# JacdacPower_50.net
KiCad netlist of a schematic drawn in Altium Designer
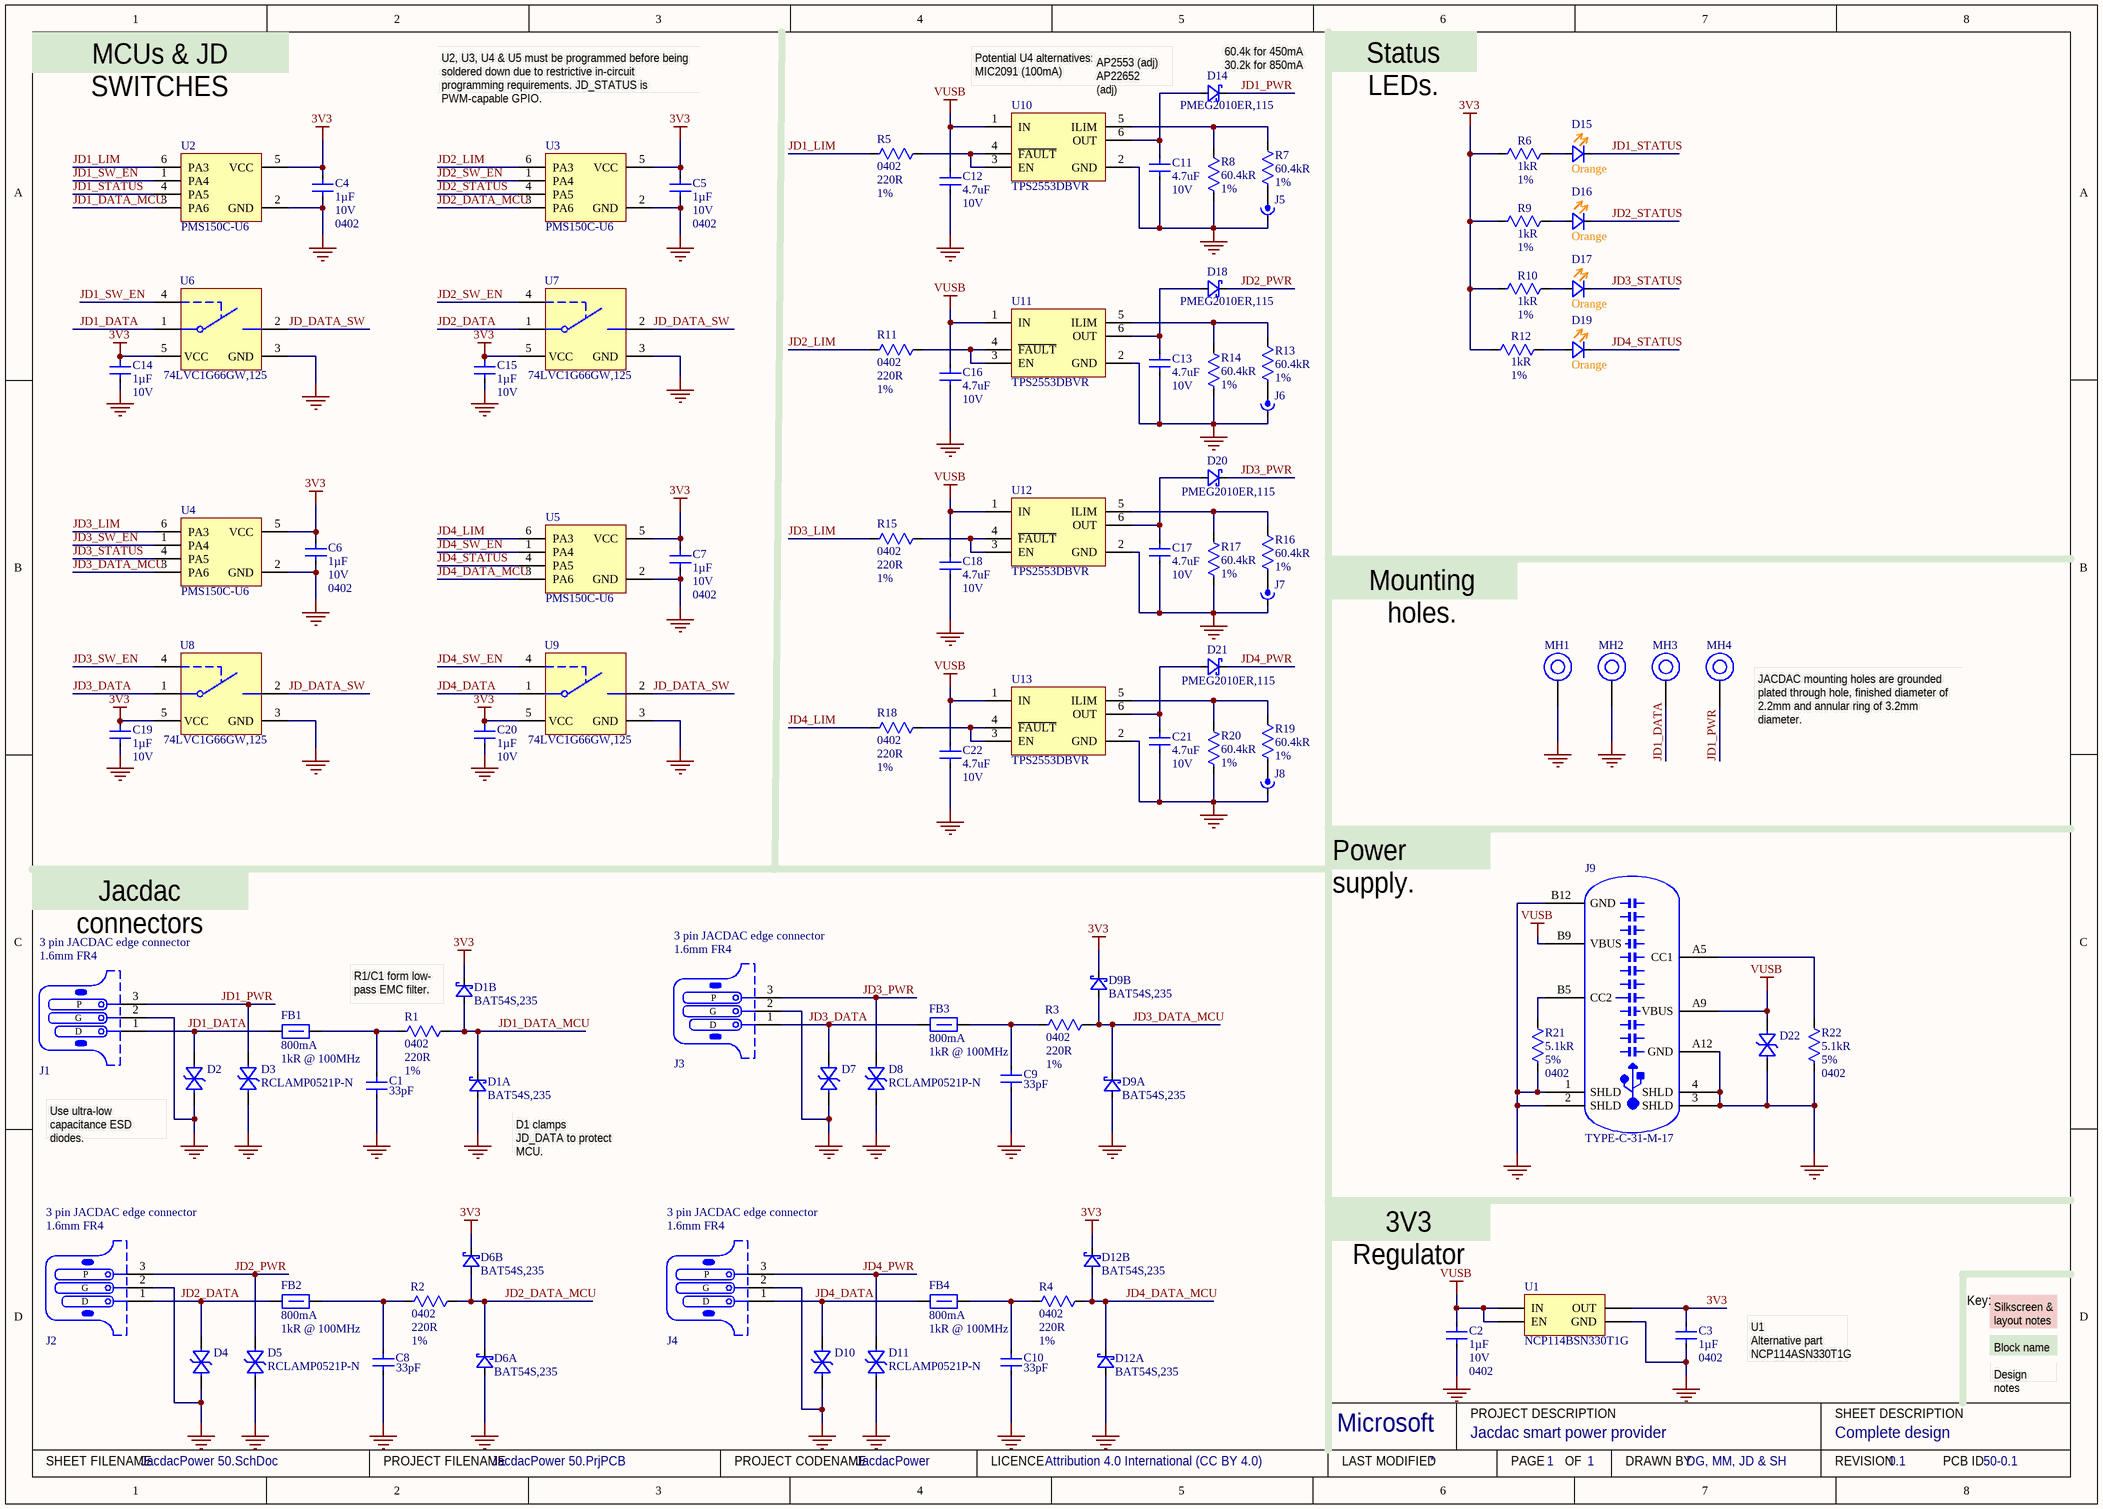
[diagram p0: JacdacPower 50.SchDoc]

(export (version "E")
  (design (tool "Eeschema 10.0.6"))
  (components
    (comp (ref "C1")
      (value "CL05C330JB5NNNC")
      (footprint "C0402_0.55MM - without outline")
      (description "CAP CER 33PF 50V C0G/NP0 0402")
      (fields
        (field (name "MANUFACTURER") "Samsung")
        (field (name "TOLERANCE") "5%")
        (field (name "CAPACITANCE") "33pF")
      )
      (libsource (lib "Samsung") (part "CL05C330JB5NNNC"))
    )
    (comp (ref "C2")
      (value "CL05A105KP5NNNC")
      (footprint "C0402_0.55MM - without outline")
      (description "CAP CER 1UF 10V X5R 0402")
      (fields
        (field (name "MANUFACTURER") "Samsung")
        (field (name "TOLERANCE") "10%")
        (field (name "CAPACITANCE") "1µF")
        (field (name "VOLTAGE RATING") "10V")
        (field (name "CASE CODE (IMPERIAL)") "0402")
      )
      (libsource (lib "Samsung") (part "CL05A105KP5NNNC"))
    )
    (comp (ref "C3")
      (value "CL05A105KP5NNNC")
      (footprint "C0402_0.55MM - without outline")
      (description "CAP CER 1UF 10V X5R 0402")
      (fields
        (field (name "MANUFACTURER") "Samsung")
        (field (name "TOLERANCE") "10%")
        (field (name "CAPACITANCE") "1µF")
        (field (name "CASE CODE (IMPERIAL)") "0402")
      )
      (libsource (lib "Samsung") (part "CL05A105KP5NNNC"))
    )
    (comp (ref "C4")
      (value "CL05A105KP5NNNC")
      (footprint "C0402_0.55MM - without outline")
      (description "CAP CER 1UF 10V X5R 0402")
      (fields
        (field (name "MANUFACTURER") "Samsung")
        (field (name "TOLERANCE") "10%")
        (field (name "CAPACITANCE") "1µF")
        (field (name "VOLTAGE RATING") "10V")
        (field (name "CASE CODE (IMPERIAL)") "0402")
      )
      (libsource (lib "Samsung") (part "CL05A105KP5NNNC"))
    )
    (comp (ref "C5")
      (value "CL05A105KP5NNNC")
      (footprint "C0402_0.55MM - without outline")
      (description "CAP CER 1UF 10V X5R 0402")
      (fields
        (field (name "MANUFACTURER") "Samsung")
        (field (name "TOLERANCE") "10%")
        (field (name "CAPACITANCE") "1µF")
        (field (name "VOLTAGE RATING") "10V")
        (field (name "CASE CODE (IMPERIAL)") "0402")
      )
      (libsource (lib "Samsung") (part "CL05A105KP5NNNC"))
    )
    (comp (ref "C6")
      (value "CL05A105KP5NNNC")
      (footprint "C0402_0.55MM - without outline")
      (description "CAP CER 1UF 10V X5R 0402")
      (fields
        (field (name "MANUFACTURER") "Samsung")
        (field (name "TOLERANCE") "10%")
        (field (name "CAPACITANCE") "1µF")
        (field (name "VOLTAGE RATING") "10V")
        (field (name "CASE CODE (IMPERIAL)") "0402")
      )
      (libsource (lib "Samsung") (part "CL05A105KP5NNNC"))
    )
    (comp (ref "C7")
      (value "CL05A105KP5NNNC")
      (footprint "C0402_0.55MM - without outline")
      (description "CAP CER 1UF 10V X5R 0402")
      (fields
        (field (name "MANUFACTURER") "Samsung")
        (field (name "TOLERANCE") "10%")
        (field (name "CAPACITANCE") "1µF")
        (field (name "VOLTAGE RATING") "10V")
        (field (name "CASE CODE (IMPERIAL)") "0402")
      )
      (libsource (lib "Samsung") (part "CL05A105KP5NNNC"))
    )
    (comp (ref "C8")
      (value "CL05C330JB5NNNC")
      (footprint "C0402_0.55MM - without outline")
      (description "CAP CER 33PF 50V C0G/NP0 0402")
      (fields
        (field (name "MANUFACTURER") "Samsung")
        (field (name "TOLERANCE") "5%")
        (field (name "CAPACITANCE") "33pF")
      )
      (libsource (lib "Samsung") (part "CL05C330JB5NNNC"))
    )
    (comp (ref "C9")
      (value "CL05C330JB5NNNC")
      (footprint "C0402_0.55MM - without outline")
      (description "CAP CER 33PF 50V C0G/NP0 0402")
      (fields
        (field (name "MANUFACTURER") "Samsung")
        (field (name "TOLERANCE") "5%")
        (field (name "CAPACITANCE") "33pF")
      )
      (libsource (lib "Samsung") (part "CL05C330JB5NNNC"))
    )
    (comp (ref "C10")
      (value "CL05C330JB5NNNC")
      (footprint "C0402_0.55MM - without outline")
      (description "CAP CER 33PF 50V C0G/NP0 0402")
      (fields
        (field (name "MANUFACTURER") "Samsung")
        (field (name "TOLERANCE") "5%")
        (field (name "CAPACITANCE") "33pF")
      )
      (libsource (lib "Samsung") (part "CL05C330JB5NNNC"))
    )
    (comp (ref "C11")
      (value "CL05A475MP5NRNC")
      (footprint "R0402 - Without outline")
      (description "CAP CER 4.7UF 10V X5R 0402")
      (fields
        (field (name "MANUFACTURER") "Samsung")
        (field (name "TOLERANCE") "20%")
        (field (name "CAPACITANCE") "4.7uF")
        (field (name "VOLTAGE RATING") "10V")
      )
      (libsource (lib "Samsung") (part "CL05A475MP5NRNC"))
    )
    (comp (ref "C12")
      (value "CL05A475MP5NRNC")
      (footprint "R0402 - Without outline")
      (description "CAP CER 4.7UF 10V X5R 0402")
      (fields
        (field (name "MANUFACTURER") "Samsung")
        (field (name "TOLERANCE") "20%")
        (field (name "CAPACITANCE") "4.7uF")
        (field (name "VOLTAGE RATING") "10V")
      )
      (libsource (lib "Samsung") (part "CL05A475MP5NRNC"))
    )
    (comp (ref "C13")
      (value "CL05A475MP5NRNC")
      (footprint "R0402 - Without outline")
      (description "CAP CER 4.7UF 10V X5R 0402")
      (fields
        (field (name "MANUFACTURER") "Samsung")
        (field (name "TOLERANCE") "20%")
        (field (name "CAPACITANCE") "4.7uF")
        (field (name "VOLTAGE RATING") "10V")
      )
      (libsource (lib "Samsung") (part "CL05A475MP5NRNC"))
    )
    (comp (ref "C14")
      (value "CL05A105KP5NNNC")
      (footprint "C0402_0.55MM - without outline")
      (description "CAP CER 1UF 10V X5R 0402")
      (fields
        (field (name "MANUFACTURER") "Samsung")
        (field (name "TOLERANCE") "10%")
        (field (name "CAPACITANCE") "1µF")
        (field (name "VOLTAGE RATING") "10V")
      )
      (libsource (lib "Samsung") (part "CL05A105KP5NNNC"))
    )
    (comp (ref "C15")
      (value "CL05A105KP5NNNC")
      (footprint "C0402_0.55MM - without outline")
      (description "CAP CER 1UF 10V X5R 0402")
      (fields
        (field (name "MANUFACTURER") "Samsung")
        (field (name "TOLERANCE") "10%")
        (field (name "CAPACITANCE") "1µF")
        (field (name "VOLTAGE RATING") "10V")
      )
      (libsource (lib "Samsung") (part "CL05A105KP5NNNC"))
    )
    (comp (ref "C16")
      (value "CL05A475MP5NRNC")
      (footprint "R0402 - Without outline")
      (description "CAP CER 4.7UF 10V X5R 0402")
      (fields
        (field (name "MANUFACTURER") "Samsung")
        (field (name "TOLERANCE") "20%")
        (field (name "CAPACITANCE") "4.7uF")
        (field (name "VOLTAGE RATING") "10V")
      )
      (libsource (lib "Samsung") (part "CL05A475MP5NRNC"))
    )
    (comp (ref "C17")
      (value "CL05A475MP5NRNC")
      (footprint "R0402 - Without outline")
      (description "CAP CER 4.7UF 10V X5R 0402")
      (fields
        (field (name "MANUFACTURER") "Samsung")
        (field (name "TOLERANCE") "20%")
        (field (name "CAPACITANCE") "4.7uF")
        (field (name "VOLTAGE RATING") "10V")
      )
      (libsource (lib "Samsung") (part "CL05A475MP5NRNC"))
    )
    (comp (ref "C18")
      (value "CL05A475MP5NRNC")
      (footprint "R0402 - Without outline")
      (description "CAP CER 4.7UF 10V X5R 0402")
      (fields
        (field (name "MANUFACTURER") "Samsung")
        (field (name "TOLERANCE") "20%")
        (field (name "CAPACITANCE") "4.7uF")
        (field (name "VOLTAGE RATING") "10V")
      )
      (libsource (lib "Samsung") (part "CL05A475MP5NRNC"))
    )
    (comp (ref "C19")
      (value "CL05A105KP5NNNC")
      (footprint "C0402_0.55MM - without outline")
      (description "CAP CER 1UF 10V X5R 0402")
      (fields
        (field (name "MANUFACTURER") "Samsung")
        (field (name "TOLERANCE") "10%")
        (field (name "CAPACITANCE") "1µF")
        (field (name "VOLTAGE RATING") "10V")
      )
      (libsource (lib "Samsung") (part "CL05A105KP5NNNC"))
    )
    (comp (ref "C20")
      (value "CL05A105KP5NNNC")
      (footprint "C0402_0.55MM - without outline")
      (description "CAP CER 1UF 10V X5R 0402")
      (fields
        (field (name "MANUFACTURER") "Samsung")
        (field (name "TOLERANCE") "10%")
        (field (name "CAPACITANCE") "1µF")
        (field (name "VOLTAGE RATING") "10V")
      )
      (libsource (lib "Samsung") (part "CL05A105KP5NNNC"))
    )
    (comp (ref "C21")
      (value "CL05A475MP5NRNC")
      (footprint "R0402 - Without outline")
      (description "CAP CER 4.7UF 10V X5R 0402")
      (fields
        (field (name "MANUFACTURER") "Samsung")
        (field (name "TOLERANCE") "20%")
        (field (name "CAPACITANCE") "4.7uF")
        (field (name "VOLTAGE RATING") "10V")
      )
      (libsource (lib "Samsung") (part "CL05A475MP5NRNC"))
    )
    (comp (ref "C22")
      (value "CL05A475MP5NRNC")
      (footprint "R0402 - Without outline")
      (description "CAP CER 4.7UF 10V X5R 0402")
      (fields
        (field (name "MANUFACTURER") "Samsung")
        (field (name "TOLERANCE") "20%")
        (field (name "CAPACITANCE") "4.7uF")
        (field (name "VOLTAGE RATING") "10V")
      )
      (libsource (lib "Samsung") (part "CL05A475MP5NRNC"))
    )
    (comp (ref "D1")
      (value "BAT54S")
      (footprint "NXP-BAT54S-TO-236AB - without outline")
      (description "DIODE ARRAY SCHOTTKY 30V SOT23")
      (fields (field (name "MANUFACTURER") "Nexperia") (field (name "MANUFACTURER PART NUMBER") "BAT54S,235"))
      (libsource (lib "NXP") (part "BAT54S"))
    )
    (comp (ref "D2")
      (value "RCLAMP0521P-N")
      (footprint "TVS 0402 - without outline")
      (description "Bidirectional 5V (Max) 6V 16V 3.5A (8/20us) 0402 TVS RoHS")
      (fields (field (name "MANUFACTURER") "Born Semiconductor"))
      (libsource (lib "BornSemiconductor") (part "RCLAMP0521P-N"))
    )
    (comp (ref "D3")
      (value "RCLAMP0521P-N")
      (footprint "TVS 0402 - without outline")
      (description "Bidirectional 5V (Max) 6V 16V 3.5A (8/20us) 0402 TVS RoHS")
      (fields
        (field (name "MANUFACTURER") "Born Semiconductor")
        (field (name "MANUFACTURER PART NUMBER") "RCLAMP0521P-N")
      )
      (libsource (lib "BornSemiconductor") (part "RCLAMP0521P-N"))
    )
    (comp (ref "D4")
      (value "RCLAMP0521P-N")
      (footprint "TVS 0402 - without outline")
      (description "Bidirectional 5V (Max) 6V 16V 3.5A (8/20us) 0402 TVS RoHS")
      (fields (field (name "MANUFACTURER") "Born Semiconductor"))
      (libsource (lib "BornSemiconductor") (part "RCLAMP0521P-N"))
    )
    (comp (ref "D5")
      (value "RCLAMP0521P-N")
      (footprint "TVS 0402 - without outline")
      (description "Bidirectional 5V (Max) 6V 16V 3.5A (8/20us) 0402 TVS RoHS")
      (fields
        (field (name "MANUFACTURER") "Born Semiconductor")
        (field (name "MANUFACTURER PART NUMBER") "RCLAMP0521P-N")
      )
      (libsource (lib "BornSemiconductor") (part "RCLAMP0521P-N"))
    )
    (comp (ref "D6")
      (value "BAT54S")
      (footprint "NXP-BAT54S-TO-236AB - without outline")
      (description "DIODE ARRAY SCHOTTKY 30V SOT23")
      (fields (field (name "MANUFACTURER") "Nexperia") (field (name "MANUFACTURER PART NUMBER") "BAT54S,235"))
      (libsource (lib "NXP") (part "BAT54S"))
    )
    (comp (ref "D7")
      (value "RCLAMP0521P-N")
      (footprint "TVS 0402 - without outline")
      (description "Bidirectional 5V (Max) 6V 16V 3.5A (8/20us) 0402 TVS RoHS")
      (fields (field (name "MANUFACTURER") "Born Semiconductor"))
      (libsource (lib "BornSemiconductor") (part "RCLAMP0521P-N"))
    )
    (comp (ref "D8")
      (value "RCLAMP0521P-N")
      (footprint "TVS 0402 - without outline")
      (description "Bidirectional 5V (Max) 6V 16V 3.5A (8/20us) 0402 TVS RoHS")
      (fields
        (field (name "MANUFACTURER") "Born Semiconductor")
        (field (name "MANUFACTURER PART NUMBER") "RCLAMP0521P-N")
      )
      (libsource (lib "BornSemiconductor") (part "RCLAMP0521P-N"))
    )
    (comp (ref "D9")
      (value "BAT54S")
      (footprint "NXP-BAT54S-TO-236AB - without outline")
      (description "DIODE ARRAY SCHOTTKY 30V SOT23")
      (fields (field (name "MANUFACTURER") "Nexperia") (field (name "MANUFACTURER PART NUMBER") "BAT54S,235"))
      (libsource (lib "NXP") (part "BAT54S"))
    )
    (comp (ref "D10")
      (value "RCLAMP0521P-N")
      (footprint "TVS 0402 - without outline")
      (description "Bidirectional 5V (Max) 6V 16V 3.5A (8/20us) 0402 TVS RoHS")
      (fields (field (name "MANUFACTURER") "Born Semiconductor"))
      (libsource (lib "BornSemiconductor") (part "RCLAMP0521P-N"))
    )
    (comp (ref "D11")
      (value "RCLAMP0521P-N")
      (footprint "TVS 0402 - without outline")
      (description "Bidirectional 5V (Max) 6V 16V 3.5A (8/20us) 0402 TVS RoHS")
      (fields
        (field (name "MANUFACTURER") "Born Semiconductor")
        (field (name "MANUFACTURER PART NUMBER") "RCLAMP0521P-N")
      )
      (libsource (lib "BornSemiconductor") (part "RCLAMP0521P-N"))
    )
    (comp (ref "D12")
      (value "BAT54S")
      (footprint "NXP-BAT54S-TO-236AB - without outline")
      (description "DIODE ARRAY SCHOTTKY 30V SOT23")
      (fields (field (name "MANUFACTURER") "Nexperia") (field (name "MANUFACTURER PART NUMBER") "BAT54S,235"))
      (libsource (lib "NXP") (part "BAT54S"))
    )
    (comp (ref "D14")
      (value "PMEG2010ER,115")
      (footprint "SOD-123W")
      (description "NEXPERIA - PMEG2010ER,115 - DIODE, RECT SCH, 20V, 1A, SOD123W")
      (fields
        (field (name "MANUFACTURER") "Nexperia")
        (field (name "MANUFACTURER PART NUMBER") "PMEG2010ER,115")
      )
      (libsource (lib "NXP") (part "PMEG2010ER,115"))
    )
    (comp (ref "D15")
      (value "~")
      (footprint "0603 Orange")
      (description "LED ORANGE DIFFUSED 0603 SMD")
      (fields
        (field (name "MANUFACTURER") "Everlight Elec")
        (field (name "MANUFACTURER PART NUMBER") "19-217/S2C-AQ1R1B/3T")
        (field (name "COLOUR") "Orange")
      )
      (libsource (lib "EverlightElec") (part "19-217/S2C-AQ1R1B/3T"))
    )
    (comp (ref "D16")
      (value "~")
      (footprint "0603 Orange")
      (description "LED ORANGE DIFFUSED 0603 SMD")
      (fields
        (field (name "MANUFACTURER") "Everlight Elec")
        (field (name "MANUFACTURER PART NUMBER") "19-217/S2C-AQ1R1B/3T")
        (field (name "COLOUR") "Orange")
      )
      (libsource (lib "EverlightElec") (part "19-217/S2C-AQ1R1B/3T"))
    )
    (comp (ref "D17")
      (value "~")
      (footprint "0603 Orange")
      (description "LED ORANGE DIFFUSED 0603 SMD")
      (fields
        (field (name "MANUFACTURER") "Everlight Elec")
        (field (name "MANUFACTURER PART NUMBER") "19-217/S2C-AQ1R1B/3T")
        (field (name "COLOUR") "Orange")
      )
      (libsource (lib "EverlightElec") (part "19-217/S2C-AQ1R1B/3T"))
    )
    (comp (ref "D18")
      (value "PMEG2010ER,115")
      (footprint "SOD-123W")
      (description "NEXPERIA - PMEG2010ER,115 - DIODE, RECT SCH, 20V, 1A, SOD123W")
      (fields
        (field (name "MANUFACTURER") "Nexperia")
        (field (name "MANUFACTURER PART NUMBER") "PMEG2010ER,115")
      )
      (libsource (lib "NXP") (part "PMEG2010ER,115"))
    )
    (comp (ref "D19")
      (value "~")
      (footprint "0603 Orange")
      (description "LED ORANGE DIFFUSED 0603 SMD")
      (fields
        (field (name "MANUFACTURER") "Everlight Elec")
        (field (name "MANUFACTURER PART NUMBER") "19-217/S2C-AQ1R1B/3T")
        (field (name "COLOUR") "Orange")
      )
      (libsource (lib "EverlightElec") (part "19-217/S2C-AQ1R1B/3T"))
    )
    (comp (ref "D20")
      (value "PMEG2010ER,115")
      (footprint "SOD-123W")
      (description "NEXPERIA - PMEG2010ER,115 - DIODE, RECT SCH, 20V, 1A, SOD123W")
      (fields
        (field (name "MANUFACTURER") "Nexperia")
        (field (name "MANUFACTURER PART NUMBER") "PMEG2010ER,115")
      )
      (libsource (lib "NXP") (part "PMEG2010ER,115"))
    )
    (comp (ref "D21")
      (value "PMEG2010ER,115")
      (footprint "SOD-123W")
      (description "NEXPERIA - PMEG2010ER,115 - DIODE, RECT SCH, 20V, 1A, SOD123W")
      (fields
        (field (name "MANUFACTURER") "Nexperia")
        (field (name "MANUFACTURER PART NUMBER") "PMEG2010ER,115")
      )
      (libsource (lib "NXP") (part "PMEG2010ER,115"))
    )
    (comp (ref "D22")
      (value "RCLAMP0521P-N")
      (footprint "TVS 0402 - without outline")
      (description "Bidirectional 5V (Max) 6V 16V 3.5A (8/20us) 0402 TVS RoHS")
      (fields (field (name "MANUFACTURER") "Born Semiconductor"))
      (libsource (lib "BornSemiconductor") (part "RCLAMP0521P-N"))
    )
    (comp (ref "FB1")
      (value "TDK MPZ1608S102ATA00")
      (footprint "TDK MPZ1608 0.8mm - without outline")
      (description "0603 1k@100MHz 0.8A chip")
      (fields
        (field (name "TOLERANCE") "25%")
        (field (name "MANUFACTURER") "TDK")
        (field (name "CURRENT RATING") "800mA")
        (field (name "IMPEDANCE") "1kR @ 100MHz")
      )
      (libsource (lib "TDK") (part "TDK MPZ1608S102ATA00"))
    )
    (comp (ref "FB2")
      (value "TDK MPZ1608S102ATA00")
      (footprint "TDK MPZ1608 0.8mm - without outline")
      (description "0603 1k@100MHz 0.8A chip")
      (fields
        (field (name "TOLERANCE") "25%")
        (field (name "MANUFACTURER") "TDK")
        (field (name "CURRENT RATING") "800mA")
        (field (name "IMPEDANCE") "1kR @ 100MHz")
      )
      (libsource (lib "TDK") (part "TDK MPZ1608S102ATA00"))
    )
    (comp (ref "FB3")
      (value "TDK MPZ1608S102ATA00")
      (footprint "TDK MPZ1608 0.8mm - without outline")
      (description "0603 1k@100MHz 0.8A chip")
      (fields
        (field (name "TOLERANCE") "25%")
        (field (name "MANUFACTURER") "TDK")
        (field (name "CURRENT RATING") "800mA")
        (field (name "IMPEDANCE") "1kR @ 100MHz")
      )
      (libsource (lib "TDK") (part "TDK MPZ1608S102ATA00"))
    )
    (comp (ref "FB4")
      (value "TDK MPZ1608S102ATA00")
      (footprint "TDK MPZ1608 0.8mm - without outline")
      (description "0603 1k@100MHz 0.8A chip")
      (fields
        (field (name "TOLERANCE") "25%")
        (field (name "MANUFACTURER") "TDK")
        (field (name "CURRENT RATING") "800mA")
        (field (name "IMPEDANCE") "1kR @ 100MHz")
      )
      (libsource (lib "TDK") (part "TDK MPZ1608S102ATA00"))
    )
    (comp (ref "J1")
      (value "3 pin JACDAC edge connector")
      (footprint "JACDAC_EDGE_CONNECTOR_0.15mm_T&G")
      (description "3 pin Jacdac edge connector 1.27mm pitch")
      (fields
        (field (name "MANUFACTURER PART NUMBER") "JACDAC_EDGE_CONNECTOR")
        (field (name "PCB TYPE") "1.6mm FR4")
      )
      (libsource (lib "generic-con") (part "Jacdac edge connector"))
    )
    (comp (ref "J2")
      (value "3 pin JACDAC edge connector")
      (footprint "JACDAC_EDGE_CONNECTOR_0.15mm_T&G")
      (description "3 pin Jacdac edge connector 1.27mm pitch")
      (fields
        (field (name "MANUFACTURER PART NUMBER") "JACDAC_EDGE_CONNECTOR")
        (field (name "PCB TYPE") "1.6mm FR4")
      )
      (libsource (lib "generic-con") (part "Jacdac edge connector"))
    )
    (comp (ref "J3")
      (value "3 pin JACDAC edge connector")
      (footprint "JACDAC_EDGE_CONNECTOR_0.15mm_T&G")
      (description "3 pin Jacdac edge connector 1.27mm pitch")
      (fields
        (field (name "MANUFACTURER PART NUMBER") "JACDAC_EDGE_CONNECTOR")
        (field (name "PCB TYPE") "1.6mm FR4")
      )
      (libsource (lib "generic-con") (part "Jacdac edge connector"))
    )
    (comp (ref "J4")
      (value "3 pin JACDAC edge connector")
      (footprint "JACDAC_EDGE_CONNECTOR_0.15mm_T&G")
      (description "3 pin Jacdac edge connector 1.27mm pitch")
      (fields
        (field (name "MANUFACTURER PART NUMBER") "JACDAC_EDGE_CONNECTOR")
        (field (name "PCB TYPE") "1.6mm FR4")
      )
      (libsource (lib "generic-con") (part "Jacdac edge connector"))
    )
    (comp (ref "J5")
      (value "OpenSolderBlob")
      (footprint "SolderBlobA")
      (description "Open solder blob")
      (libsource (lib "generic") (part "OpenSolderBlob"))
    )
    (comp (ref "J6")
      (value "OpenSolderBlob")
      (footprint "SolderBlobA")
      (description "Open solder blob")
      (libsource (lib "generic") (part "OpenSolderBlob"))
    )
    (comp (ref "J7")
      (value "OpenSolderBlob")
      (footprint "SolderBlobA")
      (description "Open solder blob")
      (libsource (lib "generic") (part "OpenSolderBlob"))
    )
    (comp (ref "J8")
      (value "OpenSolderBlob")
      (footprint "SolderBlobA")
      (description "Open solder blob")
      (libsource (lib "generic") (part "OpenSolderBlob"))
    )
    (comp (ref "J9")
      (value "TYPE-C-31-M-17")
      (footprint "TYPE-C-31-M-17")
      (description "USB - Type C Female 6 USB Connectors RoHS")
      (fields
        (field (name "MANUFACTURER") "Korean Hroparts Elec")
        (field (name "MANUFACTURER PART NUMBER") "TYPE-C-31-M-17")
      )
      (libsource (lib "KoreanHropartsElec") (part "TYPE-C-31-M-17"))
    )
    (comp (ref "MH1")
      (value "MH_5.0MMK_3.0MMC_2.1MMD_PTH")
      (footprint "MH_5.0MMK_3.0MMC_2.1MMD_PTH")
      (description "Mounting Hole 5.0mm keepout, 3.0mm annualar ring and 2.1mm Drill PTH")
      (libsource (lib "generic") (part "MH_5.0MMK_3.0MMC_2.1MMD_PTH"))
    )
    (comp (ref "MH2")
      (value "MH_5.0MMK_3.0MMC_2.1MMD_PTH")
      (footprint "MH_5.0MMK_3.0MMC_2.1MMD_PTH")
      (description "Mounting Hole 5.0mm keepout, 3.0mm annualar ring and 2.1mm Drill PTH")
      (libsource (lib "generic") (part "MH_5.0MMK_3.0MMC_2.1MMD_PTH"))
    )
    (comp (ref "MH3")
      (value "MH_5.0MMK_3.0MMC_2.1MMD_PTH")
      (footprint "MH_5.0MMK_3.0MMC_2.1MMD_PTH")
      (description "Mounting Hole 5.0mm keepout, 3.0mm annualar ring and 2.1mm Drill PTH")
      (libsource (lib "generic") (part "MH_5.0MMK_3.0MMC_2.1MMD_PTH"))
    )
    (comp (ref "MH4")
      (value "MH_5.0MMK_3.0MMC_2.1MMD_PTH")
      (footprint "MH_5.0MMK_3.0MMC_2.1MMD_PTH")
      (description "Mounting Hole 5.0mm keepout, 3.0mm annualar ring and 2.1mm Drill PTH")
      (libsource (lib "generic") (part "MH_5.0MMK_3.0MMC_2.1MMD_PTH"))
    )
    (comp (ref "R1")
      (value "RC0402FR-07220RL")
      (footprint "R0402 - Without outline")
      (description "RES SMD 220 OHM 1% 1/16W 0402")
      (fields
        (field (name "MANUFACTURER") "Yageo")
        (field (name "CASE CODE (IMPERIAL)") "0402")
        (field (name "RESISTANCE") "220R")
        (field (name "TOLERANCE") "1%")
      )
      (libsource (lib "Yageo") (part "RC0402FR-07220RL"))
    )
    (comp (ref "R2")
      (value "RC0402FR-07220RL")
      (footprint "R0402 - Without outline")
      (description "RES SMD 220 OHM 1% 1/16W 0402")
      (fields
        (field (name "MANUFACTURER") "Yageo")
        (field (name "CASE CODE (IMPERIAL)") "0402")
        (field (name "RESISTANCE") "220R")
        (field (name "TOLERANCE") "1%")
      )
      (libsource (lib "Yageo") (part "RC0402FR-07220RL"))
    )
    (comp (ref "R3")
      (value "RC0402FR-07220RL")
      (footprint "R0402 - Without outline")
      (description "RES SMD 220 OHM 1% 1/16W 0402")
      (fields
        (field (name "MANUFACTURER") "Yageo")
        (field (name "CASE CODE (IMPERIAL)") "0402")
        (field (name "RESISTANCE") "220R")
        (field (name "TOLERANCE") "1%")
      )
      (libsource (lib "Yageo") (part "RC0402FR-07220RL"))
    )
    (comp (ref "R4")
      (value "RC0402FR-07220RL")
      (footprint "R0402 - Without outline")
      (description "RES SMD 220 OHM 1% 1/16W 0402")
      (fields
        (field (name "MANUFACTURER") "Yageo")
        (field (name "CASE CODE (IMPERIAL)") "0402")
        (field (name "RESISTANCE") "220R")
        (field (name "TOLERANCE") "1%")
      )
      (libsource (lib "Yageo") (part "RC0402FR-07220RL"))
    )
    (comp (ref "R5")
      (value "RC0402FR-07220RL")
      (footprint "R0402 - Without outline")
      (description "RES SMD 220 OHM 1% 1/16W 0402")
      (fields
        (field (name "MANUFACTURER") "Yageo")
        (field (name "CASE CODE (IMPERIAL)") "0402")
        (field (name "RESISTANCE") "220R")
        (field (name "TOLERANCE") "1%")
      )
      (libsource (lib "Yageo") (part "RC0402FR-07220RL"))
    )
    (comp (ref "R6")
      (value "RC0402FR-071KL")
      (footprint "R0402 - Without outline")
      (description "RES SMD 1K OHM 1% 1/16W 0402")
      (fields
        (field (name "MANUFACTURER") "Yageo")
        (field (name "TOLERANCE") "1%")
        (field (name "RESISTANCE") "1kR")
      )
      (libsource (lib "Yageo") (part "RC0402FR-071KL"))
    )
    (comp (ref "R7")
      (value "RC0402FR-0760K4L")
      (footprint "R0402 - Without outline")
      (description "RES SMD 60.4K OHM 1% 1/16W 0402")
      (fields
        (field (name "MANUFACTURER") "Yageo")
        (field (name "RESISTANCE") "60.4kR")
        (field (name "TOLERANCE") "1%")
      )
      (libsource (lib "Yageo") (part "RC0402FR-0760K4L"))
    )
    (comp (ref "R8")
      (value "RC0402FR-0760K4L")
      (footprint "R0402 - Without outline")
      (description "RES SMD 60.4K OHM 1% 1/16W 0402")
      (fields
        (field (name "MANUFACTURER") "Yageo")
        (field (name "RESISTANCE") "60.4kR")
        (field (name "TOLERANCE") "1%")
      )
      (libsource (lib "Yageo") (part "RC0402FR-0760K4L"))
    )
    (comp (ref "R9")
      (value "RC0402FR-071KL")
      (footprint "R0402 - Without outline")
      (description "RES SMD 1K OHM 1% 1/16W 0402")
      (fields
        (field (name "MANUFACTURER") "Yageo")
        (field (name "TOLERANCE") "1%")
        (field (name "RESISTANCE") "1kR")
      )
      (libsource (lib "Yageo") (part "RC0402FR-071KL"))
    )
    (comp (ref "R10")
      (value "RC0402FR-071KL")
      (footprint "R0402 - Without outline")
      (description "RES SMD 1K OHM 1% 1/16W 0402")
      (fields
        (field (name "MANUFACTURER") "Yageo")
        (field (name "TOLERANCE") "1%")
        (field (name "RESISTANCE") "1kR")
      )
      (libsource (lib "Yageo") (part "RC0402FR-071KL"))
    )
    (comp (ref "R11")
      (value "RC0402FR-07220RL")
      (footprint "R0402 - Without outline")
      (description "RES SMD 220 OHM 1% 1/16W 0402")
      (fields
        (field (name "MANUFACTURER") "Yageo")
        (field (name "CASE CODE (IMPERIAL)") "0402")
        (field (name "RESISTANCE") "220R")
        (field (name "TOLERANCE") "1%")
      )
      (libsource (lib "Yageo") (part "RC0402FR-07220RL"))
    )
    (comp (ref "R12")
      (value "RC0402FR-071KL")
      (footprint "R0402 - Without outline")
      (description "RES SMD 1K OHM 1% 1/16W 0402")
      (fields
        (field (name "MANUFACTURER") "Yageo")
        (field (name "TOLERANCE") "1%")
        (field (name "RESISTANCE") "1kR")
      )
      (libsource (lib "Yageo") (part "RC0402FR-071KL"))
    )
    (comp (ref "R13")
      (value "RC0402FR-0760K4L")
      (footprint "R0402 - Without outline")
      (description "RES SMD 60.4K OHM 1% 1/16W 0402")
      (fields
        (field (name "MANUFACTURER") "Yageo")
        (field (name "RESISTANCE") "60.4kR")
        (field (name "TOLERANCE") "1%")
      )
      (libsource (lib "Yageo") (part "RC0402FR-0760K4L"))
    )
    (comp (ref "R14")
      (value "RC0402FR-0760K4L")
      (footprint "R0402 - Without outline")
      (description "RES SMD 60.4K OHM 1% 1/16W 0402")
      (fields
        (field (name "MANUFACTURER") "Yageo")
        (field (name "RESISTANCE") "60.4kR")
        (field (name "TOLERANCE") "1%")
      )
      (libsource (lib "Yageo") (part "RC0402FR-0760K4L"))
    )
    (comp (ref "R15")
      (value "RC0402FR-07220RL")
      (footprint "R0402 - Without outline")
      (description "RES SMD 220 OHM 1% 1/16W 0402")
      (fields
        (field (name "MANUFACTURER") "Yageo")
        (field (name "CASE CODE (IMPERIAL)") "0402")
        (field (name "RESISTANCE") "220R")
        (field (name "TOLERANCE") "1%")
      )
      (libsource (lib "Yageo") (part "RC0402FR-07220RL"))
    )
    (comp (ref "R16")
      (value "RC0402FR-0760K4L")
      (footprint "R0402 - Without outline")
      (description "RES SMD 60.4K OHM 1% 1/16W 0402")
      (fields
        (field (name "MANUFACTURER") "Yageo")
        (field (name "RESISTANCE") "60.4kR")
        (field (name "TOLERANCE") "1%")
      )
      (libsource (lib "Yageo") (part "RC0402FR-0760K4L"))
    )
    (comp (ref "R17")
      (value "RC0402FR-0760K4L")
      (footprint "R0402 - Without outline")
      (description "RES SMD 60.4K OHM 1% 1/16W 0402")
      (fields
        (field (name "MANUFACTURER") "Yageo")
        (field (name "RESISTANCE") "60.4kR")
        (field (name "TOLERANCE") "1%")
      )
      (libsource (lib "Yageo") (part "RC0402FR-0760K4L"))
    )
    (comp (ref "R18")
      (value "RC0402FR-07220RL")
      (footprint "R0402 - Without outline")
      (description "RES SMD 220 OHM 1% 1/16W 0402")
      (fields
        (field (name "MANUFACTURER") "Yageo")
        (field (name "CASE CODE (IMPERIAL)") "0402")
        (field (name "RESISTANCE") "220R")
        (field (name "TOLERANCE") "1%")
      )
      (libsource (lib "Yageo") (part "RC0402FR-07220RL"))
    )
    (comp (ref "R19")
      (value "RC0402FR-0760K4L")
      (footprint "R0402 - Without outline")
      (description "RES SMD 60.4K OHM 1% 1/16W 0402")
      (fields
        (field (name "MANUFACTURER") "Yageo")
        (field (name "RESISTANCE") "60.4kR")
        (field (name "TOLERANCE") "1%")
      )
      (libsource (lib "Yageo") (part "RC0402FR-0760K4L"))
    )
    (comp (ref "R20")
      (value "RC0402FR-0760K4L")
      (footprint "R0402 - Without outline")
      (description "RES SMD 60.4K OHM 1% 1/16W 0402")
      (fields
        (field (name "MANUFACTURER") "Yageo")
        (field (name "RESISTANCE") "60.4kR")
        (field (name "TOLERANCE") "1%")
      )
      (libsource (lib "Yageo") (part "RC0402FR-0760K4L"))
    )
    (comp (ref "R21")
      (value "RC0402JR-075K1L")
      (footprint "R0402 - Without outline")
      (description "RES SMD 5.1K OHM 5% 1/16W 0402")
      (fields
        (field (name "MANUFACTURER") "Yageo")
        (field (name "RESISTANCE") "5.1kR")
        (field (name "TOLERANCE") "5%")
        (field (name "CASE CODE (IMPERIAL)") "0402")
      )
      (libsource (lib "Yageo") (part "RC0402JR-075K1L"))
    )
    (comp (ref "R22")
      (value "RC0402JR-075K1L")
      (footprint "R0402 - Without outline")
      (description "RES SMD 5.1K OHM 5% 1/16W 0402")
      (fields
        (field (name "MANUFACTURER") "Yageo")
        (field (name "RESISTANCE") "5.1kR")
        (field (name "TOLERANCE") "5%")
        (field (name "CASE CODE (IMPERIAL)") "0402")
      )
      (libsource (lib "Yageo") (part "RC0402JR-075K1L"))
    )
    (comp (ref "U1")
      (value "LDO 3.3V/300 mA")
      (footprint "ON_SEMI-SOT23-5 - without outline")
      (description "CMOS Low Dropout Regulator (LDO), 300 mA 3.3V, Non-Active Discharge, TSOP5")
      (fields
        (field (name "MANUFACTURER") "ON Semiconductor")
        (field (name "MANUFACTURER PART NUMBER") "NCP114BSN330T1G")
      )
      (libsource (lib "OnSemiconductor") (part "NCP114BSN330T1G"))
    )
    (comp (ref "U2")
      (value "PMS150C")
      (footprint "SOT23-6")
      (description "8bit OTP Type IO Controller")
      (fields (field (name "MANUFACTURER PART NUMBER") "PMS150C-U6") (field (name "MANUFACTURER") "PADAUK"))
      (libsource (lib "PADAUK") (part "PMS150C"))
    )
    (comp (ref "U3")
      (value "PMS150C")
      (footprint "SOT23-6")
      (description "8bit OTP Type IO Controller")
      (fields (field (name "MANUFACTURER PART NUMBER") "PMS150C-U6") (field (name "MANUFACTURER") "PADAUK"))
      (libsource (lib "PADAUK") (part "PMS150C"))
    )
    (comp (ref "U4")
      (value "PMS150C")
      (footprint "SOT23-6")
      (description "8bit OTP Type IO Controller")
      (fields (field (name "MANUFACTURER PART NUMBER") "PMS150C-U6") (field (name "MANUFACTURER") "PADAUK"))
      (libsource (lib "PADAUK") (part "PMS150C"))
    )
    (comp (ref "U5")
      (value "PMS150C")
      (footprint "SOT23-6")
      (description "8bit OTP Type IO Controller")
      (fields (field (name "MANUFACTURER PART NUMBER") "PMS150C-U6") (field (name "MANUFACTURER") "PADAUK"))
      (libsource (lib "PADAUK") (part "PMS150C"))
    )
    (comp (ref "U6")
      (value "74LVC1G66GW,125")
      (footprint "TSSOP-5/SOT353-1")
      (description "Analog Switch Single SPST 5-Pin TSSOP T/R")
      (fields
        (field (name "MANUFACTURER") "Nexperia")
        (field (name "MANUFACTURER PART NUMBER") "74LVC1G66GW,125")
      )
      (libsource (lib "Nexperia") (part "74LVC1G66GW,125"))
    )
    (comp (ref "U7")
      (value "74LVC1G66GW,125")
      (footprint "TSSOP-5/SOT353-1")
      (description "Analog Switch Single SPST 5-Pin TSSOP T/R")
      (fields
        (field (name "MANUFACTURER") "Nexperia")
        (field (name "MANUFACTURER PART NUMBER") "74LVC1G66GW,125")
      )
      (libsource (lib "Nexperia") (part "74LVC1G66GW,125"))
    )
    (comp (ref "U8")
      (value "74LVC1G66GW,125")
      (footprint "TSSOP-5/SOT353-1")
      (description "Analog Switch Single SPST 5-Pin TSSOP T/R")
      (fields
        (field (name "MANUFACTURER") "Nexperia")
        (field (name "MANUFACTURER PART NUMBER") "74LVC1G66GW,125")
      )
      (libsource (lib "Nexperia") (part "74LVC1G66GW,125"))
    )
    (comp (ref "U9")
      (value "74LVC1G66GW,125")
      (footprint "TSSOP-5/SOT353-1")
      (description "Analog Switch Single SPST 5-Pin TSSOP T/R")
      (fields
        (field (name "MANUFACTURER") "Nexperia")
        (field (name "MANUFACTURER PART NUMBER") "74LVC1G66GW,125")
      )
      (libsource (lib "Nexperia") (part "74LVC1G66GW,125"))
    )
    (comp (ref "U10")
      (value "TPS2553DBVR")
      (footprint "TI-TPS2553 - without_outline")
      (fields (field (name "MANUFACTURER PART NUMBER") "TPS2553DBVR"))
      (libsource (lib "TexasInstruments") (part "TPS2553DBVR"))
    )
    (comp (ref "U11")
      (value "TPS2553DBVR")
      (footprint "TI-TPS2553 - without_outline")
      (fields (field (name "MANUFACTURER PART NUMBER") "TPS2553DBVR"))
      (libsource (lib "TexasInstruments") (part "TPS2553DBVR"))
    )
    (comp (ref "U12")
      (value "TPS2553DBVR")
      (footprint "TI-TPS2553 - without_outline")
      (fields (field (name "MANUFACTURER PART NUMBER") "TPS2553DBVR"))
      (libsource (lib "TexasInstruments") (part "TPS2553DBVR"))
    )
    (comp (ref "U13")
      (value "TPS2553DBVR")
      (footprint "TI-TPS2553 - without_outline")
      (fields (field (name "MANUFACTURER PART NUMBER") "TPS2553DBVR"))
      (libsource (lib "TexasInstruments") (part "TPS2553DBVR"))
    )
  )
  (nets
    (net (code "1") (name "/JD1_DATA") (class "Default")
      (node (ref "D2") (pin "1") (pinfunction "K_1") (pintype "passive"))
      (node (ref "FB1") (pin "1") (pinfunction "1_1") (pintype "passive"))
      (node (ref "J1") (pin "1") (pinfunction "D_1") (pintype "passive"))
      (node (ref "MH3") (pin "1") (pinfunction "1_1") (pintype "passive"))
      (node (ref "U6") (pin "1") (pinfunction "Y_1") (pintype "passive"))
    )
    (net (code "2") (name "/JD1_DATA_MCU") (class "Default")
      (node (ref "D1") (pin "3") (pinfunction "A_3") (pintype "passive"))
      (node (ref "R1") (pin "1") (pinfunction "1_1") (pintype "passive"))
      (node (ref "U2") (pin "3") (pinfunction "PA6_3") (pintype "passive"))
    )
    (net (code "3") (name "/JD1_LIM") (class "Default")
      (node (ref "R5") (pin "2") (pinfunction "2_2") (pintype "passive"))
      (node (ref "U2") (pin "6") (pinfunction "PA3_6") (pintype "passive"))
    )
    (net (code "4") (name "/JD1_PWR") (class "Default")
      (node (ref "D14") (pin "1") (pinfunction "K_1") (pintype "passive"))
      (node (ref "D3") (pin "1") (pinfunction "K_1") (pintype "passive"))
      (node (ref "J1") (pin "3") (pinfunction "P_3") (pintype "passive"))
      (node (ref "MH4") (pin "1") (pinfunction "1_1") (pintype "passive"))
    )
    (net (code "5") (name "/JD1_STATUS") (class "Default")
      (node (ref "D15") (pin "1") (pinfunction "K_1") (pintype "passive"))
      (node (ref "U2") (pin "4") (pinfunction "PA5_4") (pintype "passive"))
    )
    (net (code "6") (name "/JD1_SW_EN") (class "Default")
      (node (ref "U2") (pin "1") (pinfunction "PA4_1") (pintype "passive"))
      (node (ref "U6") (pin "4") (pinfunction "EN_4") (pintype "passive"))
    )
    (net (code "7") (name "/JD2_DATA") (class "Default")
      (node (ref "D4") (pin "1") (pinfunction "K_1") (pintype "passive"))
      (node (ref "FB2") (pin "1") (pinfunction "1_1") (pintype "passive"))
      (node (ref "J2") (pin "1") (pinfunction "D_1") (pintype "passive"))
      (node (ref "U7") (pin "1") (pinfunction "Y_1") (pintype "passive"))
    )
    (net (code "8") (name "/JD2_DATA_MCU") (class "Default")
      (node (ref "D6") (pin "3") (pinfunction "K_3") (pintype "passive"))
      (node (ref "R2") (pin "1") (pinfunction "1_1") (pintype "passive"))
      (node (ref "U3") (pin "3") (pinfunction "PA6_3") (pintype "passive"))
    )
    (net (code "9") (name "/JD2_LIM") (class "Default")
      (node (ref "R11") (pin "2") (pinfunction "2_2") (pintype "passive"))
      (node (ref "U3") (pin "6") (pinfunction "PA3_6") (pintype "passive"))
    )
    (net (code "10") (name "/JD2_PWR") (class "Default")
      (node (ref "D18") (pin "1") (pinfunction "K_1") (pintype "passive"))
      (node (ref "D5") (pin "1") (pinfunction "K_1") (pintype "passive"))
      (node (ref "J2") (pin "3") (pinfunction "P_3") (pintype "passive"))
    )
    (net (code "11") (name "/JD2_STATUS") (class "Default")
      (node (ref "D16") (pin "1") (pinfunction "K_1") (pintype "passive"))
      (node (ref "U3") (pin "4") (pinfunction "PA5_4") (pintype "passive"))
    )
    (net (code "12") (name "/JD2_SW_EN") (class "Default")
      (node (ref "U3") (pin "1") (pinfunction "PA4_1") (pintype "passive"))
      (node (ref "U7") (pin "4") (pinfunction "EN_4") (pintype "passive"))
    )
    (net (code "13") (name "/JD3_DATA") (class "Default")
      (node (ref "D7") (pin "1") (pinfunction "K_1") (pintype "passive"))
      (node (ref "FB3") (pin "1") (pinfunction "1_1") (pintype "passive"))
      (node (ref "J3") (pin "1") (pinfunction "D_1") (pintype "passive"))
      (node (ref "U8") (pin "1") (pinfunction "Y_1") (pintype "passive"))
    )
    (net (code "14") (name "/JD3_DATA_MCU") (class "Default")
      (node (ref "D9") (pin "3") (pinfunction "K_3") (pintype "passive"))
      (node (ref "R3") (pin "1") (pinfunction "1_1") (pintype "passive"))
      (node (ref "U4") (pin "3") (pinfunction "PA6_3") (pintype "passive"))
    )
    (net (code "15") (name "/JD3_LIM") (class "Default")
      (node (ref "R15") (pin "2") (pinfunction "2_2") (pintype "passive"))
      (node (ref "U4") (pin "6") (pinfunction "PA3_6") (pintype "passive"))
    )
    (net (code "16") (name "/JD3_PWR") (class "Default")
      (node (ref "D20") (pin "1") (pinfunction "K_1") (pintype "passive"))
      (node (ref "D8") (pin "1") (pinfunction "K_1") (pintype "passive"))
      (node (ref "J3") (pin "3") (pinfunction "P_3") (pintype "passive"))
    )
    (net (code "17") (name "/JD3_STATUS") (class "Default")
      (node (ref "D17") (pin "1") (pinfunction "K_1") (pintype "passive"))
      (node (ref "U4") (pin "4") (pinfunction "PA5_4") (pintype "passive"))
    )
    (net (code "18") (name "/JD3_SW_EN") (class "Default")
      (node (ref "U4") (pin "1") (pinfunction "PA4_1") (pintype "passive"))
      (node (ref "U8") (pin "4") (pinfunction "EN_4") (pintype "passive"))
    )
    (net (code "19") (name "/JD4_DATA") (class "Default")
      (node (ref "D10") (pin "1") (pinfunction "K_1") (pintype "passive"))
      (node (ref "FB4") (pin "1") (pinfunction "1_1") (pintype "passive"))
      (node (ref "J4") (pin "1") (pinfunction "D_1") (pintype "passive"))
      (node (ref "U9") (pin "1") (pinfunction "Y_1") (pintype "passive"))
    )
    (net (code "20") (name "/JD4_DATA_MCU") (class "Default")
      (node (ref "D12") (pin "3") (pinfunction "K_3") (pintype "passive"))
      (node (ref "R4") (pin "1") (pinfunction "1_1") (pintype "passive"))
      (node (ref "U5") (pin "3") (pinfunction "PA6_3") (pintype "passive"))
    )
    (net (code "21") (name "/JD4_LIM") (class "Default")
      (node (ref "R18") (pin "2") (pinfunction "2_2") (pintype "passive"))
      (node (ref "U5") (pin "6") (pinfunction "PA3_6") (pintype "passive"))
    )
    (net (code "22") (name "/JD4_PWR") (class "Default")
      (node (ref "D11") (pin "1") (pinfunction "K_1") (pintype "passive"))
      (node (ref "D21") (pin "1") (pinfunction "K_1") (pintype "passive"))
      (node (ref "J4") (pin "3") (pinfunction "P_3") (pintype "passive"))
    )
    (net (code "23") (name "/JD4_STATUS") (class "Default")
      (node (ref "D19") (pin "1") (pinfunction "K_1") (pintype "passive"))
      (node (ref "U5") (pin "4") (pinfunction "PA5_4") (pintype "passive"))
    )
    (net (code "24") (name "/JD4_SW_EN") (class "Default")
      (node (ref "U5") (pin "1") (pinfunction "PA4_1") (pintype "passive"))
      (node (ref "U9") (pin "4") (pinfunction "EN_4") (pintype "passive"))
    )
    (net (code "25") (name "/JD_DATA_SW") (class "Default")
      (node (ref "U6") (pin "2") (pinfunction "Z_2") (pintype "passive"))
      (node (ref "U7") (pin "2") (pinfunction "Z_2") (pintype "passive"))
      (node (ref "U8") (pin "2") (pinfunction "Z_2") (pintype "passive"))
      (node (ref "U9") (pin "2") (pinfunction "Z_2") (pintype "passive"))
    )
    (net (code "26") (name "3V3") (class "Default")
      (node (ref "C14") (pin "2") (pinfunction "2_2") (pintype "passive"))
      (node (ref "C15") (pin "2") (pinfunction "2_2") (pintype "passive"))
      (node (ref "C19") (pin "2") (pinfunction "2_2") (pintype "passive"))
      (node (ref "C20") (pin "2") (pinfunction "2_2") (pintype "passive"))
      (node (ref "C3") (pin "2") (pinfunction "2_2") (pintype "passive"))
      (node (ref "C4") (pin "2") (pinfunction "2_2") (pintype "passive"))
      (node (ref "C5") (pin "2") (pinfunction "2_2") (pintype "passive"))
      (node (ref "C6") (pin "2") (pinfunction "2_2") (pintype "passive"))
      (node (ref "C7") (pin "2") (pinfunction "2_2") (pintype "passive"))
      (node (ref "D1") (pin "2") (pinfunction "K_2") (pintype "passive"))
      (node (ref "D12") (pin "2") (pinfunction "K_2") (pintype "passive"))
      (node (ref "D6") (pin "2") (pinfunction "K_2") (pintype "passive"))
      (node (ref "D9") (pin "2") (pinfunction "K_2") (pintype "passive"))
      (node (ref "R10") (pin "2") (pinfunction "2_2") (pintype "passive"))
      (node (ref "R12") (pin "2") (pinfunction "2_2") (pintype "passive"))
      (node (ref "R6") (pin "2") (pinfunction "2_2") (pintype "passive"))
      (node (ref "R9") (pin "2") (pinfunction "2_2") (pintype "passive"))
      (node (ref "U1") (pin "5") (pinfunction "OUT_5") (pintype "passive"))
      (node (ref "U2") (pin "5") (pinfunction "VCC_5") (pintype "passive"))
      (node (ref "U3") (pin "5") (pinfunction "VCC_5") (pintype "passive"))
      (node (ref "U4") (pin "5") (pinfunction "VCC_5") (pintype "passive"))
      (node (ref "U5") (pin "5") (pinfunction "VCC_5") (pintype "passive"))
      (node (ref "U6") (pin "5") (pinfunction "VCC_5") (pintype "passive"))
      (node (ref "U7") (pin "5") (pinfunction "VCC_5") (pintype "passive"))
      (node (ref "U8") (pin "5") (pinfunction "VCC_5") (pintype "passive"))
      (node (ref "U9") (pin "5") (pinfunction "VCC_5") (pintype "passive"))
    )
    (net (code "27") (name "GND") (class "Default")
      (node (ref "C1") (pin "1") (pinfunction "1_1") (pintype "passive"))
      (node (ref "C10") (pin "1") (pinfunction "1_1") (pintype "passive"))
      (node (ref "C11") (pin "1") (pinfunction "1_1") (pintype "passive"))
      (node (ref "C12") (pin "1") (pinfunction "1_1") (pintype "passive"))
      (node (ref "C13") (pin "1") (pinfunction "1_1") (pintype "passive"))
      (node (ref "C14") (pin "1") (pinfunction "1_1") (pintype "passive"))
      (node (ref "C15") (pin "1") (pinfunction "1_1") (pintype "passive"))
      (node (ref "C16") (pin "1") (pinfunction "1_1") (pintype "passive"))
      (node (ref "C17") (pin "1") (pinfunction "1_1") (pintype "passive"))
      (node (ref "C18") (pin "1") (pinfunction "1_1") (pintype "passive"))
      (node (ref "C19") (pin "1") (pinfunction "1_1") (pintype "passive"))
      (node (ref "C2") (pin "1") (pinfunction "1_1") (pintype "passive"))
      (node (ref "C20") (pin "1") (pinfunction "1_1") (pintype "passive"))
      (node (ref "C21") (pin "1") (pinfunction "1_1") (pintype "passive"))
      (node (ref "C22") (pin "1") (pinfunction "1_1") (pintype "passive"))
      (node (ref "C3") (pin "1") (pinfunction "1_1") (pintype "passive"))
      (node (ref "C4") (pin "1") (pinfunction "1_1") (pintype "passive"))
      (node (ref "C5") (pin "1") (pinfunction "1_1") (pintype "passive"))
      (node (ref "C6") (pin "1") (pinfunction "1_1") (pintype "passive"))
      (node (ref "C7") (pin "1") (pinfunction "1_1") (pintype "passive"))
      (node (ref "C8") (pin "1") (pinfunction "1_1") (pintype "passive"))
      (node (ref "C9") (pin "1") (pinfunction "1_1") (pintype "passive"))
      (node (ref "D1") (pin "1") (pinfunction "A_1") (pintype "passive"))
      (node (ref "D10") (pin "2") (pinfunction "A_2") (pintype "passive"))
      (node (ref "D11") (pin "2") (pinfunction "A_2") (pintype "passive"))
      (node (ref "D12") (pin "1") (pinfunction "A_1") (pintype "passive"))
      (node (ref "D2") (pin "2") (pinfunction "A_2") (pintype "passive"))
      (node (ref "D22") (pin "2") (pinfunction "A_2") (pintype "passive"))
      (node (ref "D3") (pin "2") (pinfunction "A_2") (pintype "passive"))
      (node (ref "D4") (pin "2") (pinfunction "A_2") (pintype "passive"))
      (node (ref "D5") (pin "2") (pinfunction "A_2") (pintype "passive"))
      (node (ref "D6") (pin "1") (pinfunction "A_1") (pintype "passive"))
      (node (ref "D7") (pin "2") (pinfunction "A_2") (pintype "passive"))
      (node (ref "D8") (pin "2") (pinfunction "A_2") (pintype "passive"))
      (node (ref "D9") (pin "1") (pinfunction "A_1") (pintype "passive"))
      (node (ref "J1") (pin "2") (pinfunction "G_2") (pintype "passive"))
      (node (ref "J2") (pin "2") (pinfunction "G_2") (pintype "passive"))
      (node (ref "J3") (pin "2") (pinfunction "G_2") (pintype "passive"))
      (node (ref "J4") (pin "2") (pinfunction "G_2") (pintype "passive"))
      (node (ref "J5") (pin "2") (pinfunction "2_2") (pintype "passive"))
      (node (ref "J6") (pin "2") (pinfunction "2_2") (pintype "passive"))
      (node (ref "J7") (pin "2") (pinfunction "2_2") (pintype "passive"))
      (node (ref "J8") (pin "2") (pinfunction "2_2") (pintype "passive"))
      (node (ref "J9") (pin "1") (pinfunction "SHLD_1") (pintype "passive"))
      (node (ref "J9") (pin "2") (pinfunction "SHLD_2") (pintype "passive"))
      (node (ref "J9") (pin "3") (pinfunction "SHLD_3") (pintype "passive"))
      (node (ref "J9") (pin "4") (pinfunction "SHLD_4") (pintype "passive"))
      (node (ref "J9") (pin "A12") (pinfunction "GND_A12") (pintype "passive"))
      (node (ref "J9") (pin "B12") (pinfunction "GND_B12") (pintype "passive"))
      (node (ref "MH1") (pin "1") (pinfunction "1_1") (pintype "passive"))
      (node (ref "MH2") (pin "1") (pinfunction "1_1") (pintype "passive"))
      (node (ref "R14") (pin "1") (pinfunction "1_1") (pintype "passive"))
      (node (ref "R17") (pin "1") (pinfunction "1_1") (pintype "passive"))
      (node (ref "R20") (pin "1") (pinfunction "1_1") (pintype "passive"))
      (node (ref "R21") (pin "2") (pinfunction "2_2") (pintype "passive"))
      (node (ref "R22") (pin "2") (pinfunction "2_2") (pintype "passive"))
      (node (ref "R8") (pin "1") (pinfunction "1_1") (pintype "passive"))
      (node (ref "U1") (pin "2") (pinfunction "GND_2") (pintype "passive"))
      (node (ref "U10") (pin "2") (pinfunction "GND_2") (pintype "passive"))
      (node (ref "U11") (pin "2") (pinfunction "GND_2") (pintype "passive"))
      (node (ref "U12") (pin "2") (pinfunction "GND_2") (pintype "passive"))
      (node (ref "U13") (pin "2") (pinfunction "GND_2") (pintype "passive"))
      (node (ref "U2") (pin "2") (pinfunction "GND_2") (pintype "passive"))
      (node (ref "U3") (pin "2") (pinfunction "GND_2") (pintype "passive"))
      (node (ref "U4") (pin "2") (pinfunction "GND_2") (pintype "passive"))
      (node (ref "U5") (pin "2") (pinfunction "GND_2") (pintype "passive"))
      (node (ref "U6") (pin "3") (pinfunction "GND_3") (pintype "passive"))
      (node (ref "U7") (pin "3") (pinfunction "GND_3") (pintype "passive"))
      (node (ref "U8") (pin "3") (pinfunction "GND_3") (pintype "passive"))
      (node (ref "U9") (pin "3") (pinfunction "GND_3") (pintype "passive"))
    )
    (net (code "28") (name "Net-(C1-Pad2)") (class "Default")
      (node (ref "C1") (pin "2") (pinfunction "2_2") (pintype "passive"))
      (node (ref "FB1") (pin "2") (pinfunction "2_2") (pintype "passive"))
      (node (ref "R1") (pin "2") (pinfunction "2_2") (pintype "passive"))
    )
    (net (code "29") (name "Net-(C8-Pad2)") (class "Default")
      (node (ref "C8") (pin "2") (pinfunction "2_2") (pintype "passive"))
      (node (ref "FB2") (pin "2") (pinfunction "2_2") (pintype "passive"))
      (node (ref "R2") (pin "2") (pinfunction "2_2") (pintype "passive"))
    )
    (net (code "30") (name "Net-(C9-Pad2)") (class "Default")
      (node (ref "C9") (pin "2") (pinfunction "2_2") (pintype "passive"))
      (node (ref "FB3") (pin "2") (pinfunction "2_2") (pintype "passive"))
      (node (ref "R3") (pin "2") (pinfunction "2_2") (pintype "passive"))
    )
    (net (code "31") (name "Net-(C10-Pad2)") (class "Default")
      (node (ref "C10") (pin "2") (pinfunction "2_2") (pintype "passive"))
      (node (ref "FB4") (pin "2") (pinfunction "2_2") (pintype "passive"))
      (node (ref "R4") (pin "2") (pinfunction "2_2") (pintype "passive"))
    )
    (net (code "32") (name "Net-(D14-A)") (class "Default")
      (node (ref "C11") (pin "2") (pinfunction "2_2") (pintype "passive"))
      (node (ref "D14") (pin "2") (pinfunction "A_2") (pintype "passive"))
      (node (ref "U10") (pin "6") (pinfunction "OUT_6") (pintype "passive"))
    )
    (net (code "33") (name "Net-(D15-A)") (class "Default")
      (node (ref "D15") (pin "2") (pinfunction "A_2") (pintype "passive"))
      (node (ref "R6") (pin "1") (pinfunction "1_1") (pintype "passive"))
    )
    (net (code "34") (name "Net-(D16-A)") (class "Default")
      (node (ref "D16") (pin "2") (pinfunction "A_2") (pintype "passive"))
      (node (ref "R9") (pin "1") (pinfunction "1_1") (pintype "passive"))
    )
    (net (code "35") (name "Net-(D17-A)") (class "Default")
      (node (ref "D17") (pin "2") (pinfunction "A_2") (pintype "passive"))
      (node (ref "R10") (pin "1") (pinfunction "1_1") (pintype "passive"))
    )
    (net (code "36") (name "Net-(D18-A)") (class "Default")
      (node (ref "C13") (pin "2") (pinfunction "2_2") (pintype "passive"))
      (node (ref "D18") (pin "2") (pinfunction "A_2") (pintype "passive"))
      (node (ref "U11") (pin "6") (pinfunction "OUT_6") (pintype "passive"))
    )
    (net (code "37") (name "Net-(D19-A)") (class "Default")
      (node (ref "D19") (pin "2") (pinfunction "A_2") (pintype "passive"))
      (node (ref "R12") (pin "1") (pinfunction "1_1") (pintype "passive"))
    )
    (net (code "38") (name "Net-(D20-A)") (class "Default")
      (node (ref "C17") (pin "2") (pinfunction "2_2") (pintype "passive"))
      (node (ref "D20") (pin "2") (pinfunction "A_2") (pintype "passive"))
      (node (ref "U12") (pin "6") (pinfunction "OUT_6") (pintype "passive"))
    )
    (net (code "39") (name "Net-(D21-A)") (class "Default")
      (node (ref "C21") (pin "2") (pinfunction "2_2") (pintype "passive"))
      (node (ref "D21") (pin "2") (pinfunction "A_2") (pintype "passive"))
      (node (ref "U13") (pin "6") (pinfunction "OUT_6") (pintype "passive"))
    )
    (net (code "40") (name "Net-(J5-Pad1)") (class "Default")
      (node (ref "J5") (pin "1") (pinfunction "1_1") (pintype "passive"))
      (node (ref "R7") (pin "1") (pinfunction "1_1") (pintype "passive"))
    )
    (net (code "41") (name "Net-(J6-Pad1)") (class "Default")
      (node (ref "J6") (pin "1") (pinfunction "1_1") (pintype "passive"))
      (node (ref "R13") (pin "1") (pinfunction "1_1") (pintype "passive"))
    )
    (net (code "42") (name "Net-(J7-Pad1)") (class "Default")
      (node (ref "J7") (pin "1") (pinfunction "1_1") (pintype "passive"))
      (node (ref "R16") (pin "1") (pinfunction "1_1") (pintype "passive"))
    )
    (net (code "43") (name "Net-(J8-Pad1)") (class "Default")
      (node (ref "J8") (pin "1") (pinfunction "1_1") (pintype "passive"))
      (node (ref "R19") (pin "1") (pinfunction "1_1") (pintype "passive"))
    )
    (net (code "44") (name "Net-(J9-CC1)") (class "Default")
      (node (ref "J9") (pin "A5") (pinfunction "CC1_A5") (pintype "passive"))
      (node (ref "R22") (pin "1") (pinfunction "1_1") (pintype "passive"))
    )
    (net (code "45") (name "Net-(J9-CC2)") (class "Default")
      (node (ref "J9") (pin "B5") (pinfunction "CC2_B5") (pintype "passive"))
      (node (ref "R21") (pin "1") (pinfunction "1_1") (pintype "passive"))
    )
    (net (code "46") (name "Net-(U10-EN)") (class "Default")
      (node (ref "R5") (pin "1") (pinfunction "1_1") (pintype "passive"))
      (node (ref "U10") (pin "3") (pinfunction "EN_3") (pintype "passive"))
      (node (ref "U10") (pin "4") (pinfunction "~{FAULT}_4") (pintype "passive"))
    )
    (net (code "47") (name "Net-(U10-ILIM)") (class "Default")
      (node (ref "R7") (pin "2") (pinfunction "2_2") (pintype "passive"))
      (node (ref "R8") (pin "2") (pinfunction "2_2") (pintype "passive"))
      (node (ref "U10") (pin "5") (pinfunction "ILIM_5") (pintype "passive"))
    )
    (net (code "48") (name "Net-(U11-EN)") (class "Default")
      (node (ref "R11") (pin "1") (pinfunction "1_1") (pintype "passive"))
      (node (ref "U11") (pin "3") (pinfunction "EN_3") (pintype "passive"))
      (node (ref "U11") (pin "4") (pinfunction "~{FAULT}_4") (pintype "passive"))
    )
    (net (code "49") (name "Net-(U11-ILIM)") (class "Default")
      (node (ref "R13") (pin "2") (pinfunction "2_2") (pintype "passive"))
      (node (ref "R14") (pin "2") (pinfunction "2_2") (pintype "passive"))
      (node (ref "U11") (pin "5") (pinfunction "ILIM_5") (pintype "passive"))
    )
    (net (code "50") (name "Net-(U12-EN)") (class "Default")
      (node (ref "R15") (pin "1") (pinfunction "1_1") (pintype "passive"))
      (node (ref "U12") (pin "3") (pinfunction "EN_3") (pintype "passive"))
      (node (ref "U12") (pin "4") (pinfunction "~{FAULT}_4") (pintype "passive"))
    )
    (net (code "51") (name "Net-(U12-ILIM)") (class "Default")
      (node (ref "R16") (pin "2") (pinfunction "2_2") (pintype "passive"))
      (node (ref "R17") (pin "2") (pinfunction "2_2") (pintype "passive"))
      (node (ref "U12") (pin "5") (pinfunction "ILIM_5") (pintype "passive"))
    )
    (net (code "52") (name "Net-(U13-EN)") (class "Default")
      (node (ref "R18") (pin "1") (pinfunction "1_1") (pintype "passive"))
      (node (ref "U13") (pin "3") (pinfunction "EN_3") (pintype "passive"))
      (node (ref "U13") (pin "4") (pinfunction "~{FAULT}_4") (pintype "passive"))
    )
    (net (code "53") (name "Net-(U13-ILIM)") (class "Default")
      (node (ref "R19") (pin "2") (pinfunction "2_2") (pintype "passive"))
      (node (ref "R20") (pin "2") (pinfunction "2_2") (pintype "passive"))
      (node (ref "U13") (pin "5") (pinfunction "ILIM_5") (pintype "passive"))
    )
    (net (code "54") (name "VUSB") (class "Default")
      (node (ref "C12") (pin "2") (pinfunction "2_2") (pintype "passive"))
      (node (ref "C16") (pin "2") (pinfunction "2_2") (pintype "passive"))
      (node (ref "C18") (pin "2") (pinfunction "2_2") (pintype "passive"))
      (node (ref "C2") (pin "2") (pinfunction "2_2") (pintype "passive"))
      (node (ref "C22") (pin "2") (pinfunction "2_2") (pintype "passive"))
      (node (ref "D22") (pin "1") (pinfunction "K_1") (pintype "passive"))
      (node (ref "J9") (pin "A9") (pinfunction "VBUS_A9") (pintype "passive"))
      (node (ref "J9") (pin "B9") (pinfunction "VBUS_B9") (pintype "passive"))
      (node (ref "U1") (pin "1") (pinfunction "IN_1") (pintype "passive"))
      (node (ref "U1") (pin "3") (pinfunction "EN_3") (pintype "passive"))
      (node (ref "U10") (pin "1") (pinfunction "IN_1") (pintype "passive"))
      (node (ref "U11") (pin "1") (pinfunction "IN_1") (pintype "passive"))
      (node (ref "U12") (pin "1") (pinfunction "IN_1") (pintype "passive"))
      (node (ref "U13") (pin "1") (pinfunction "IN_1") (pintype "passive"))
    )
  )
)
